# nola4.net
KiCad netlist of a schematic drawn in EAGLE
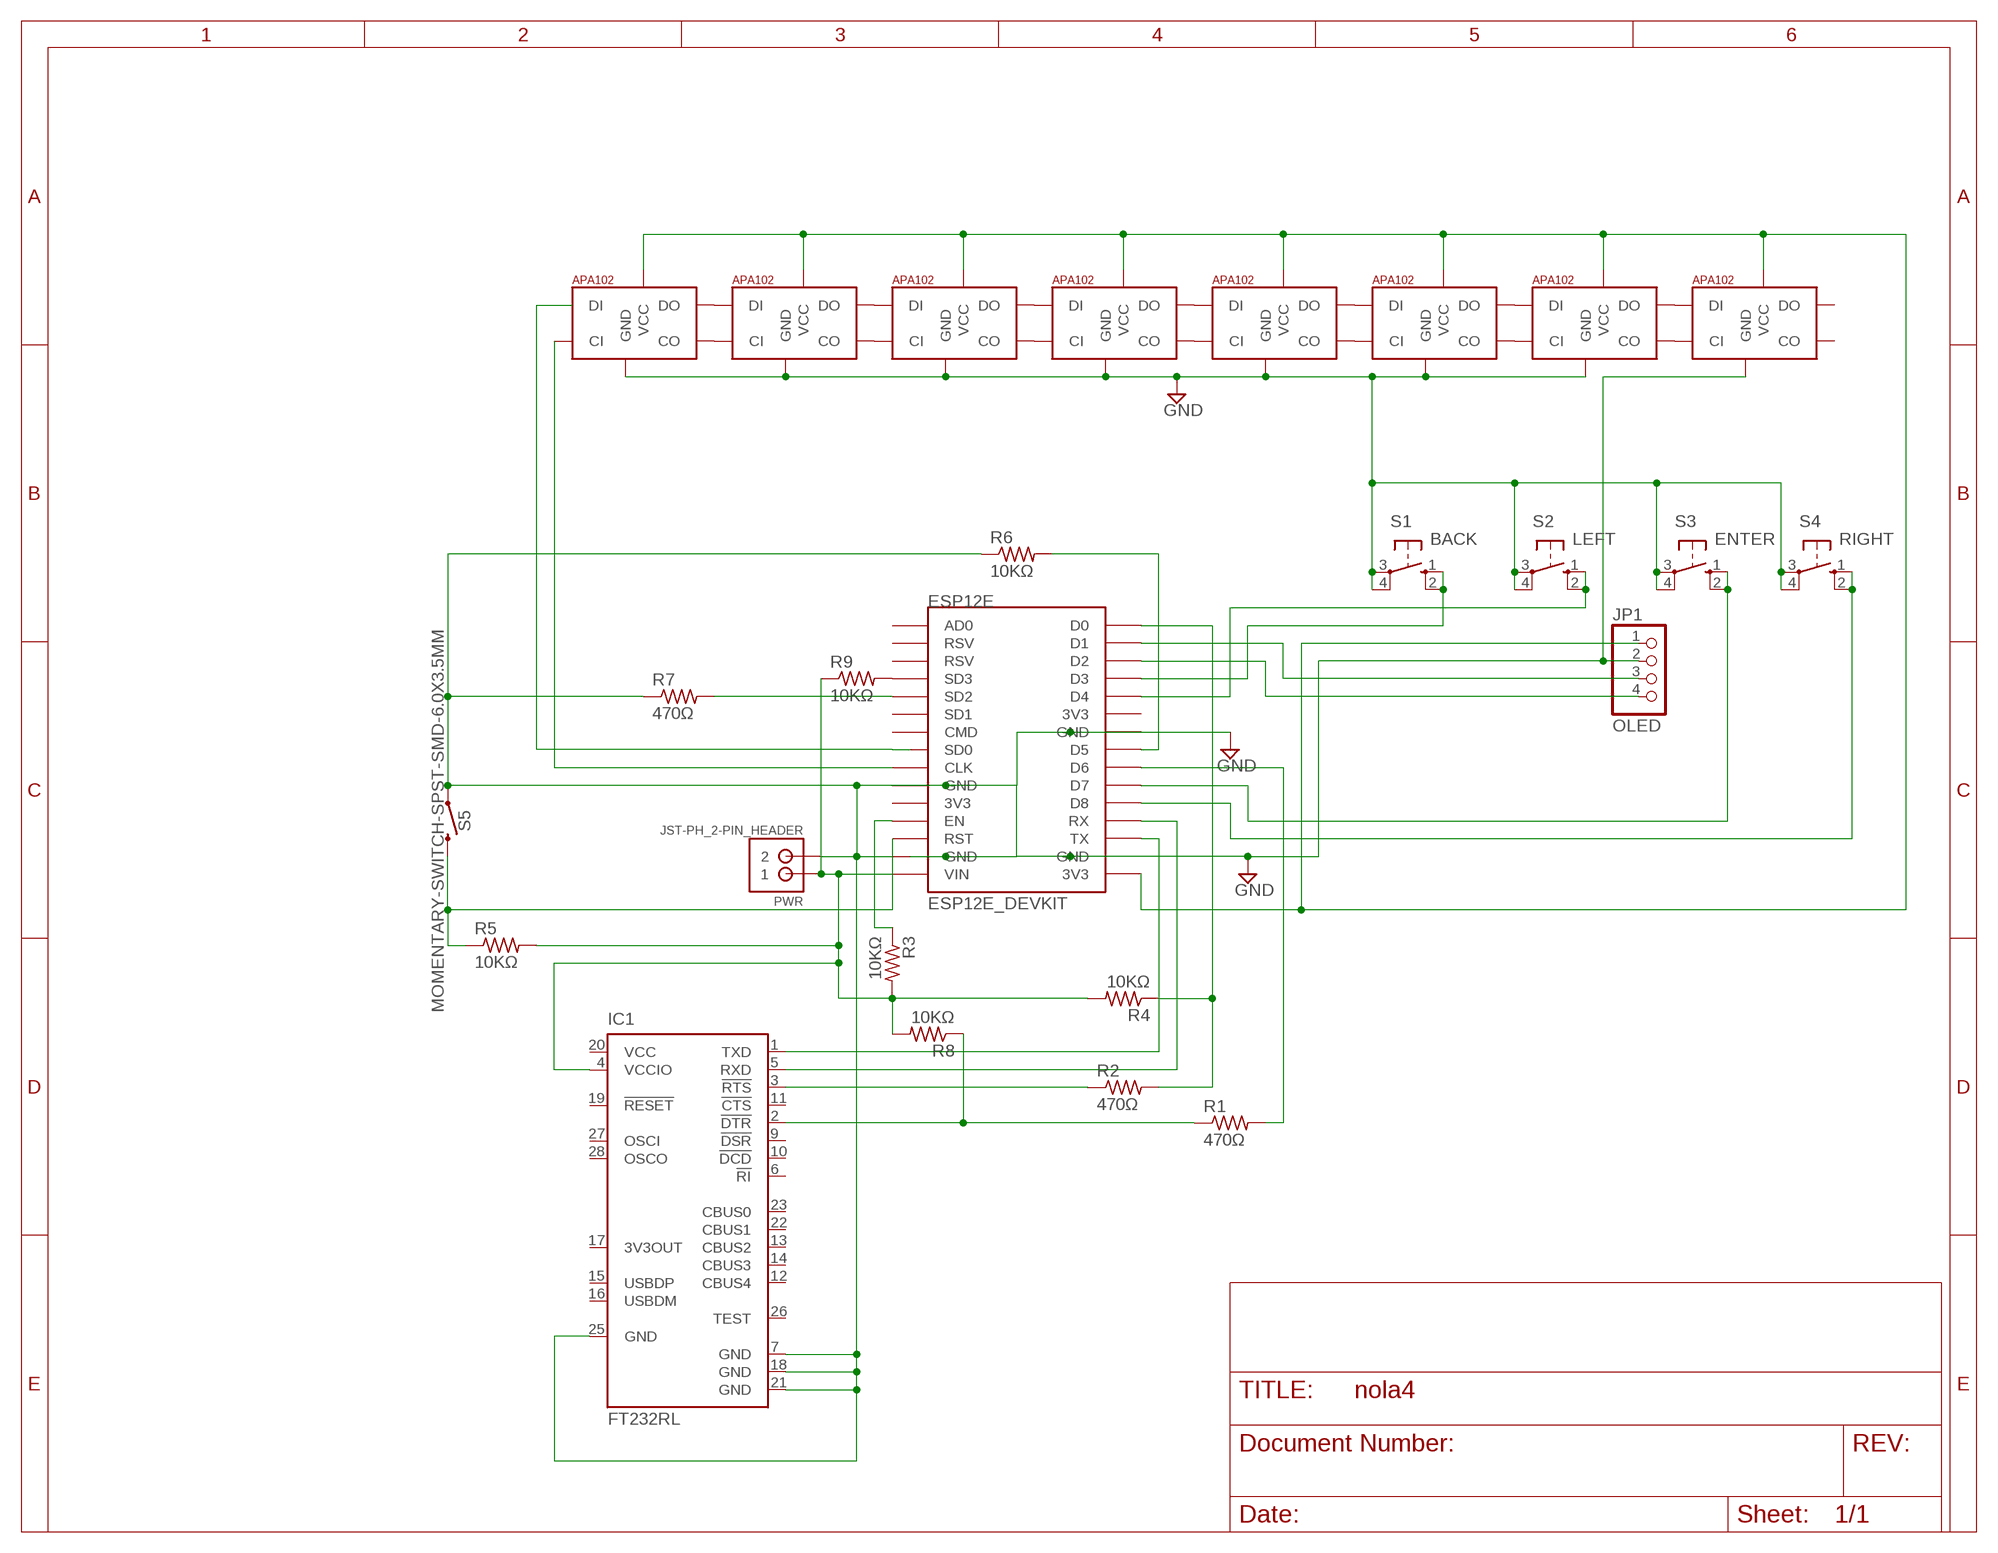
[diagram p0: schematic, sheet 1]

(export (version "E")
  (design (tool "Eeschema 10.0.6"))
  (components
    (comp (ref "ESP12E")
      (value "ESP12E_DEVKIT")
      (footprint "eagle-import:ESP12E_DEVKIT")
      (libsource (lib "eagle-import") (part "ESP12E_DEVKIT"))
    )
    (comp (ref "IC1")
      (value "FT232RL")
      (footprint "eagle-import:SSOP28")
      (libsource (lib "eagle-import") (part "FT232RL"))
    )
    (comp (ref "JP1")
      (value "OLED")
      (footprint "eagle-import:1X04")
      (libsource (lib "eagle-import") (part "PINHD-1X4"))
    )
    (comp (ref "LED1")
      (value "APA1025050")
      (footprint "eagle-import:APA102_5050")
      (libsource (lib "eagle-import") (part "APA1025050"))
    )
    (comp (ref "LED2")
      (value "APA1025050")
      (footprint "eagle-import:APA102_5050")
      (libsource (lib "eagle-import") (part "APA1025050"))
    )
    (comp (ref "LED3")
      (value "APA1025050")
      (footprint "eagle-import:APA102_5050")
      (libsource (lib "eagle-import") (part "APA1025050"))
    )
    (comp (ref "LED4")
      (value "APA1025050")
      (footprint "eagle-import:APA102_5050")
      (libsource (lib "eagle-import") (part "APA1025050"))
    )
    (comp (ref "LED5")
      (value "APA1025050")
      (footprint "eagle-import:APA102_5050")
      (libsource (lib "eagle-import") (part "APA1025050"))
    )
    (comp (ref "LED6")
      (value "APA1025050")
      (footprint "eagle-import:APA102_5050")
      (libsource (lib "eagle-import") (part "APA1025050"))
    )
    (comp (ref "LED7")
      (value "APA1025050")
      (footprint "eagle-import:APA102_5050")
      (libsource (lib "eagle-import") (part "APA1025050"))
    )
    (comp (ref "LED8")
      (value "APA1025050")
      (footprint "eagle-import:APA102_5050")
      (libsource (lib "eagle-import") (part "APA1025050"))
    )
    (comp (ref "PWR")
      (value "JST-PH_2-PIN_HEADER")
      (footprint "eagle-import:JST_B2B-PH_HEADER")
      (libsource (lib "eagle-import") (part "JST-PH_2-PIN_HEADER"))
    )
    (comp (ref "R1")
      (value "470Ω")
      (footprint "eagle-import:R0805")
      (libsource (lib "eagle-import") (part "R-US_R0805"))
    )
    (comp (ref "R2")
      (value "470Ω")
      (footprint "eagle-import:R0805")
      (libsource (lib "eagle-import") (part "R-US_R0805"))
    )
    (comp (ref "R3")
      (value "10KΩ")
      (footprint "eagle-import:R0805")
      (libsource (lib "eagle-import") (part "R-US_R0805"))
    )
    (comp (ref "R4")
      (value "10KΩ")
      (footprint "eagle-import:R0805")
      (libsource (lib "eagle-import") (part "R-US_R0805"))
    )
    (comp (ref "R5")
      (value "10KΩ")
      (footprint "eagle-import:R0805")
      (libsource (lib "eagle-import") (part "R-US_R0805"))
    )
    (comp (ref "R6")
      (value "10KΩ")
      (footprint "eagle-import:R0805")
      (libsource (lib "eagle-import") (part "R-US_R0805"))
    )
    (comp (ref "R7")
      (value "470Ω")
      (footprint "eagle-import:R0805")
      (libsource (lib "eagle-import") (part "R-US_R0805"))
    )
    (comp (ref "R8")
      (value "10KΩ")
      (footprint "eagle-import:R0805")
      (libsource (lib "eagle-import") (part "R-US_R0805"))
    )
    (comp (ref "R9")
      (value "10KΩ")
      (footprint "eagle-import:R0805")
      (libsource (lib "eagle-import") (part "R-US_R0805"))
    )
    (comp (ref "S1")
      (value "BACK")
      (footprint "eagle-import:B3F-10XX")
      (fields (field (name "MPN") "B3F-1000"))
      (libsource (lib "eagle-import") (part "10-XX"))
    )
    (comp (ref "S2")
      (value "LEFT")
      (footprint "eagle-import:B3F-10XX")
      (fields (field (name "MPN") "B3F-1000"))
      (libsource (lib "eagle-import") (part "10-XX"))
    )
    (comp (ref "S3")
      (value "ENTER")
      (footprint "eagle-import:B3F-10XX")
      (fields (field (name "MPN") "B3F-1000"))
      (libsource (lib "eagle-import") (part "10-XX"))
    )
    (comp (ref "S4")
      (value "RIGHT")
      (footprint "eagle-import:B3F-10XX")
      (fields (field (name "MPN") "B3F-1000"))
      (libsource (lib "eagle-import") (part "10-XX"))
    )
    (comp (ref "S5")
      (value "MOMENTARY-SWITCH-SPST-SMD-6.0X3.5MM")
      (footprint "eagle-import:TACTILE_SWITCH_SMD_6.0X3.5MM")
      (libsource (lib "eagle-import") (part "MOMENTARY-SWITCH-SPST-SMD-6.0X3.5MM"))
    )
  )
  (nets
    (net (code "1") (name "/VCC") (class "Default")
      (node (ref "IC1") (pin "20") (pinfunction "VCC_20") (pintype "power_in"))
    )
    (net (code "2") (name "GND") (class "Default")
      (node (ref "ESP12E") (pin "GND@0") (pinfunction "GND_GND@0") (pintype "bidirectional"))
      (node (ref "ESP12E") (pin "GND@1") (pinfunction "GND_GND@1") (pintype "bidirectional"))
      (node (ref "ESP12E") (pin "GND@2") (pinfunction "GND_GND@2") (pintype "bidirectional"))
      (node (ref "ESP12E") (pin "GND@3") (pinfunction "GND_GND@3") (pintype "bidirectional"))
      (node (ref "IC1") (pin "18") (pinfunction "GND_18") (pintype "power_in"))
      (node (ref "IC1") (pin "21") (pinfunction "GND_21") (pintype "power_in"))
      (node (ref "IC1") (pin "25") (pinfunction "GND_25") (pintype "power_in"))
      (node (ref "IC1") (pin "7") (pinfunction "GND_7") (pintype "power_in"))
      (node (ref "JP1") (pin "2") (pinfunction "2_2") (pintype "passive"))
      (node (ref "LED1") (pin "6") (pinfunction "GND_6") (pintype "bidirectional"))
      (node (ref "LED2") (pin "6") (pinfunction "GND_6") (pintype "bidirectional"))
      (node (ref "LED3") (pin "6") (pinfunction "GND_6") (pintype "bidirectional"))
      (node (ref "LED4") (pin "6") (pinfunction "GND_6") (pintype "bidirectional"))
      (node (ref "LED5") (pin "6") (pinfunction "GND_6") (pintype "bidirectional"))
      (node (ref "LED6") (pin "6") (pinfunction "GND_6") (pintype "bidirectional"))
      (node (ref "LED7") (pin "6") (pinfunction "GND_6") (pintype "bidirectional"))
      (node (ref "LED8") (pin "6") (pinfunction "GND_6") (pintype "bidirectional"))
      (node (ref "PWR") (pin "P2") (pinfunction "2_P2") (pintype "bidirectional"))
      (node (ref "R6") (pin "1") (pinfunction "1_1") (pintype "passive"))
      (node (ref "R7") (pin "1") (pinfunction "1_1") (pintype "passive"))
      (node (ref "S1") (pin "3") (pinfunction "P_3") (pintype "passive"))
      (node (ref "S1") (pin "4") (pinfunction "P1_4") (pintype "passive"))
      (node (ref "S2") (pin "3") (pinfunction "P_3") (pintype "passive"))
      (node (ref "S2") (pin "4") (pinfunction "P1_4") (pintype "passive"))
      (node (ref "S3") (pin "3") (pinfunction "P_3") (pintype "passive"))
      (node (ref "S3") (pin "4") (pinfunction "P1_4") (pintype "passive"))
      (node (ref "S4") (pin "3") (pinfunction "P_3") (pintype "passive"))
      (node (ref "S4") (pin "4") (pinfunction "P1_4") (pintype "passive"))
      (node (ref "S5") (pin "1") (pinfunction "1_1") (pintype "passive"))
    )
    (net (code "3") (name "Net-(ESP12E-PadD1)") (class "Default")
      (node (ref "ESP12E") (pin "D1") (pinfunction "D1_D1") (pintype "bidirectional"))
      (node (ref "JP1") (pin "3") (pinfunction "3_3") (pintype "passive"))
    )
    (net (code "4") (name "Net-(ESP12E-PadD2)") (class "Default")
      (node (ref "ESP12E") (pin "D2") (pinfunction "D2_D2") (pintype "bidirectional"))
      (node (ref "JP1") (pin "4") (pinfunction "4_4") (pintype "passive"))
    )
    (net (code "5") (name "Net-(ESP12E-PadD5)") (class "Default")
      (node (ref "ESP12E") (pin "D5") (pinfunction "D5_D5") (pintype "bidirectional"))
      (node (ref "R6") (pin "2") (pinfunction "2_2") (pintype "passive"))
    )
    (net (code "6") (name "Net-(ESP12E-PadD6)") (class "Default")
      (node (ref "ESP12E") (pin "D6") (pinfunction "D6_D6") (pintype "bidirectional"))
      (node (ref "R1") (pin "2") (pinfunction "2_2") (pintype "passive"))
    )
    (net (code "7") (name "Net-(ESP12E-PadEN)") (class "Default")
      (node (ref "ESP12E") (pin "EN") (pinfunction "EN_EN") (pintype "bidirectional"))
      (node (ref "R3") (pin "1") (pinfunction "1_1") (pintype "passive"))
    )
    (net (code "8") (name "Net-(ESP12E-PadRST)") (class "Default")
      (node (ref "ESP12E") (pin "RST") (pinfunction "RST_RST") (pintype "bidirectional"))
      (node (ref "R5") (pin "1") (pinfunction "1_1") (pintype "passive"))
      (node (ref "S5") (pin "2") (pinfunction "2_2") (pintype "passive"))
    )
    (net (code "9") (name "Net-(ESP12E-PadSD2)") (class "Default")
      (node (ref "ESP12E") (pin "SD2") (pinfunction "SD2_SD2") (pintype "bidirectional"))
      (node (ref "R7") (pin "2") (pinfunction "2_2") (pintype "passive"))
    )
    (net (code "10") (name "Net-(ESP12E-PadSD3)") (class "Default")
      (node (ref "ESP12E") (pin "SD3") (pinfunction "SD3_SD3") (pintype "bidirectional"))
      (node (ref "R9") (pin "2") (pinfunction "2_2") (pintype "passive"))
    )
    (net (code "11") (name "Net-(IC1-RXD)") (class "Default")
      (node (ref "ESP12E") (pin "RX") (pinfunction "RX_RX") (pintype "bidirectional"))
      (node (ref "IC1") (pin "5") (pinfunction "RXD_5") (pintype "input"))
    )
    (net (code "12") (name "Net-(IC1-TXD)") (class "Default")
      (node (ref "ESP12E") (pin "D0") (pinfunction "D0_D0") (pintype "bidirectional"))
      (node (ref "ESP12E") (pin "TX") (pinfunction "TX_TX") (pintype "bidirectional"))
      (node (ref "IC1") (pin "1") (pinfunction "TXD_1") (pintype "output"))
      (node (ref "R2") (pin "2") (pinfunction "2_2") (pintype "passive"))
      (node (ref "R4") (pin "1") (pinfunction "1_1") (pintype "passive"))
    )
    (net (code "13") (name "Net-(IC1-VCCIO)") (class "Default")
      (node (ref "ESP12E") (pin "VIN") (pinfunction "VIN_VIN") (pintype "bidirectional"))
      (node (ref "IC1") (pin "4") (pinfunction "VCCIO_4") (pintype "power_in"))
      (node (ref "PWR") (pin "P1") (pinfunction "1_P1") (pintype "bidirectional"))
      (node (ref "R3") (pin "2") (pinfunction "2_2") (pintype "passive"))
      (node (ref "R4") (pin "2") (pinfunction "2_2") (pintype "passive"))
      (node (ref "R5") (pin "2") (pinfunction "2_2") (pintype "passive"))
      (node (ref "R8") (pin "2") (pinfunction "2_2") (pintype "passive"))
      (node (ref "R9") (pin "1") (pinfunction "1_1") (pintype "passive"))
    )
    (net (code "14") (name "Net-(IC1-~{DTR})") (class "Default")
      (node (ref "IC1") (pin "2") (pinfunction "~{DTR}_2") (pintype "output"))
      (node (ref "R1") (pin "1") (pinfunction "1_1") (pintype "passive"))
      (node (ref "R8") (pin "1") (pinfunction "1_1") (pintype "passive"))
    )
    (net (code "15") (name "Net-(IC1-~{RTS})") (class "Default")
      (node (ref "IC1") (pin "3") (pinfunction "~{RTS}_3") (pintype "output"))
      (node (ref "R2") (pin "1") (pinfunction "1_1") (pintype "passive"))
    )
    (net (code "16") (name "Net-(LED1-CI)") (class "Default")
      (node (ref "ESP12E") (pin "CLK") (pinfunction "CLK_CLK") (pintype "bidirectional"))
      (node (ref "LED1") (pin "5") (pinfunction "CI_5") (pintype "bidirectional"))
    )
    (net (code "17") (name "Net-(LED1-CO)") (class "Default")
      (node (ref "LED1") (pin "2") (pinfunction "CO_2") (pintype "bidirectional"))
      (node (ref "LED2") (pin "5") (pinfunction "CI_5") (pintype "bidirectional"))
    )
    (net (code "18") (name "Net-(LED1-DI)") (class "Default")
      (node (ref "ESP12E") (pin "SD0") (pinfunction "SD0_SD0") (pintype "bidirectional"))
      (node (ref "LED1") (pin "4") (pinfunction "DI_4") (pintype "bidirectional"))
    )
    (net (code "19") (name "Net-(LED1-DO)") (class "Default")
      (node (ref "LED1") (pin "3") (pinfunction "DO_3") (pintype "bidirectional"))
      (node (ref "LED2") (pin "4") (pinfunction "DI_4") (pintype "bidirectional"))
    )
    (net (code "20") (name "Net-(LED1-VCC)") (class "Default")
      (node (ref "ESP12E") (pin "3V3@2") (pinfunction "3V3_3V3@2") (pintype "bidirectional"))
      (node (ref "JP1") (pin "1") (pinfunction "1_1") (pintype "passive"))
      (node (ref "LED1") (pin "1") (pinfunction "VCC_1") (pintype "bidirectional"))
      (node (ref "LED2") (pin "1") (pinfunction "VCC_1") (pintype "bidirectional"))
      (node (ref "LED3") (pin "1") (pinfunction "VCC_1") (pintype "bidirectional"))
      (node (ref "LED4") (pin "1") (pinfunction "VCC_1") (pintype "bidirectional"))
      (node (ref "LED5") (pin "1") (pinfunction "VCC_1") (pintype "bidirectional"))
      (node (ref "LED6") (pin "1") (pinfunction "VCC_1") (pintype "bidirectional"))
      (node (ref "LED7") (pin "1") (pinfunction "VCC_1") (pintype "bidirectional"))
      (node (ref "LED8") (pin "1") (pinfunction "VCC_1") (pintype "bidirectional"))
    )
    (net (code "21") (name "Net-(LED2-CO)") (class "Default")
      (node (ref "LED2") (pin "2") (pinfunction "CO_2") (pintype "bidirectional"))
      (node (ref "LED3") (pin "5") (pinfunction "CI_5") (pintype "bidirectional"))
    )
    (net (code "22") (name "Net-(LED2-DO)") (class "Default")
      (node (ref "LED2") (pin "3") (pinfunction "DO_3") (pintype "bidirectional"))
      (node (ref "LED3") (pin "4") (pinfunction "DI_4") (pintype "bidirectional"))
    )
    (net (code "23") (name "Net-(LED3-CO)") (class "Default")
      (node (ref "LED3") (pin "2") (pinfunction "CO_2") (pintype "bidirectional"))
      (node (ref "LED4") (pin "5") (pinfunction "CI_5") (pintype "bidirectional"))
    )
    (net (code "24") (name "Net-(LED3-DO)") (class "Default")
      (node (ref "LED3") (pin "3") (pinfunction "DO_3") (pintype "bidirectional"))
      (node (ref "LED4") (pin "4") (pinfunction "DI_4") (pintype "bidirectional"))
    )
    (net (code "25") (name "Net-(LED4-CO)") (class "Default")
      (node (ref "LED4") (pin "2") (pinfunction "CO_2") (pintype "bidirectional"))
      (node (ref "LED5") (pin "5") (pinfunction "CI_5") (pintype "bidirectional"))
    )
    (net (code "26") (name "Net-(LED4-DO)") (class "Default")
      (node (ref "LED4") (pin "3") (pinfunction "DO_3") (pintype "bidirectional"))
      (node (ref "LED5") (pin "4") (pinfunction "DI_4") (pintype "bidirectional"))
    )
    (net (code "27") (name "Net-(LED5-CO)") (class "Default")
      (node (ref "LED5") (pin "2") (pinfunction "CO_2") (pintype "bidirectional"))
      (node (ref "LED6") (pin "5") (pinfunction "CI_5") (pintype "bidirectional"))
    )
    (net (code "28") (name "Net-(LED5-DO)") (class "Default")
      (node (ref "LED5") (pin "3") (pinfunction "DO_3") (pintype "bidirectional"))
      (node (ref "LED6") (pin "4") (pinfunction "DI_4") (pintype "bidirectional"))
    )
    (net (code "29") (name "Net-(LED6-CO)") (class "Default")
      (node (ref "LED6") (pin "2") (pinfunction "CO_2") (pintype "bidirectional"))
      (node (ref "LED7") (pin "5") (pinfunction "CI_5") (pintype "bidirectional"))
    )
    (net (code "30") (name "Net-(LED6-DO)") (class "Default")
      (node (ref "LED6") (pin "3") (pinfunction "DO_3") (pintype "bidirectional"))
      (node (ref "LED7") (pin "4") (pinfunction "DI_4") (pintype "bidirectional"))
    )
    (net (code "31") (name "Net-(LED7-CO)") (class "Default")
      (node (ref "LED7") (pin "2") (pinfunction "CO_2") (pintype "bidirectional"))
      (node (ref "LED8") (pin "5") (pinfunction "CI_5") (pintype "bidirectional"))
    )
    (net (code "32") (name "Net-(LED7-DO)") (class "Default")
      (node (ref "LED7") (pin "3") (pinfunction "DO_3") (pintype "bidirectional"))
      (node (ref "LED8") (pin "4") (pinfunction "DI_4") (pintype "bidirectional"))
    )
    (net (code "33") (name "Net-(S1-S)") (class "Default")
      (node (ref "ESP12E") (pin "D3") (pinfunction "D3_D3") (pintype "bidirectional"))
      (node (ref "S1") (pin "1") (pinfunction "S_1") (pintype "passive"))
      (node (ref "S1") (pin "2") (pinfunction "S1_2") (pintype "passive"))
    )
    (net (code "34") (name "Net-(S2-S)") (class "Default")
      (node (ref "ESP12E") (pin "D4") (pinfunction "D4_D4") (pintype "bidirectional"))
      (node (ref "S2") (pin "1") (pinfunction "S_1") (pintype "passive"))
      (node (ref "S2") (pin "2") (pinfunction "S1_2") (pintype "passive"))
    )
    (net (code "35") (name "Net-(S3-S)") (class "Default")
      (node (ref "ESP12E") (pin "D7") (pinfunction "D7_D7") (pintype "bidirectional"))
      (node (ref "S3") (pin "1") (pinfunction "S_1") (pintype "passive"))
      (node (ref "S3") (pin "2") (pinfunction "S1_2") (pintype "passive"))
    )
    (net (code "36") (name "Net-(S4-S)") (class "Default")
      (node (ref "ESP12E") (pin "D8") (pinfunction "D8_D8") (pintype "bidirectional"))
      (node (ref "S4") (pin "1") (pinfunction "S_1") (pintype "passive"))
      (node (ref "S4") (pin "2") (pinfunction "S1_2") (pintype "passive"))
    )
    (net (code "37") (name "unconnected-(ESP12E-3V3-Pad3V3@0)") (class "Default")
      (node (ref "ESP12E") (pin "3V3@0") (pinfunction "3V3_3V3@0") (pintype "bidirectional"))
    )
    (net (code "38") (name "unconnected-(ESP12E-3V3-Pad3V3@1)") (class "Default")
      (node (ref "ESP12E") (pin "3V3@1") (pinfunction "3V3_3V3@1") (pintype "bidirectional"))
    )
    (net (code "39") (name "unconnected-(ESP12E-PadAD0)") (class "Default")
      (node (ref "ESP12E") (pin "AD0") (pinfunction "AD0_AD0") (pintype "bidirectional"))
    )
    (net (code "40") (name "unconnected-(ESP12E-PadCMD)") (class "Default")
      (node (ref "ESP12E") (pin "CMD") (pinfunction "CMD_CMD") (pintype "bidirectional"))
    )
    (net (code "41") (name "unconnected-(ESP12E-PadSD1)") (class "Default")
      (node (ref "ESP12E") (pin "SD1") (pinfunction "SD1_SD1") (pintype "bidirectional"))
    )
    (net (code "42") (name "unconnected-(ESP12E-RSV-PadRSV@0)") (class "Default")
      (node (ref "ESP12E") (pin "RSV@0") (pinfunction "RSV_RSV@0") (pintype "bidirectional"))
    )
    (net (code "43") (name "unconnected-(ESP12E-RSV-PadRSV@1)") (class "Default")
      (node (ref "ESP12E") (pin "RSV@1") (pinfunction "RSV_RSV@1") (pintype "bidirectional"))
    )
    (net (code "44") (name "unconnected-(IC1-3V3OUT-Pad17)") (class "Default")
      (node (ref "IC1") (pin "17") (pinfunction "3V3OUT_17") (pintype "output"))
    )
    (net (code "45") (name "unconnected-(IC1-CBUS0-Pad23)") (class "Default")
      (node (ref "IC1") (pin "23") (pinfunction "CBUS0_23") (pintype "bidirectional"))
    )
    (net (code "46") (name "unconnected-(IC1-CBUS1-Pad22)") (class "Default")
      (node (ref "IC1") (pin "22") (pinfunction "CBUS1_22") (pintype "bidirectional"))
    )
    (net (code "47") (name "unconnected-(IC1-CBUS2-Pad13)") (class "Default")
      (node (ref "IC1") (pin "13") (pinfunction "CBUS2_13") (pintype "bidirectional"))
    )
    (net (code "48") (name "unconnected-(IC1-CBUS3-Pad14)") (class "Default")
      (node (ref "IC1") (pin "14") (pinfunction "CBUS3_14") (pintype "bidirectional"))
    )
    (net (code "49") (name "unconnected-(IC1-CBUS4-Pad12)") (class "Default")
      (node (ref "IC1") (pin "12") (pinfunction "CBUS4_12") (pintype "bidirectional"))
    )
    (net (code "50") (name "unconnected-(IC1-OSCI-Pad27)") (class "Default")
      (node (ref "IC1") (pin "27") (pinfunction "OSCI_27") (pintype "input"))
    )
    (net (code "51") (name "unconnected-(IC1-OSCO-Pad28)") (class "Default")
      (node (ref "IC1") (pin "28") (pinfunction "OSCO_28") (pintype "output"))
    )
    (net (code "52") (name "unconnected-(IC1-TEST-Pad26)") (class "Default")
      (node (ref "IC1") (pin "26") (pinfunction "TEST_26") (pintype "input"))
    )
    (net (code "53") (name "unconnected-(IC1-USBDM-Pad16)") (class "Default")
      (node (ref "IC1") (pin "16") (pinfunction "USBDM_16") (pintype "bidirectional"))
    )
    (net (code "54") (name "unconnected-(IC1-USBDP-Pad15)") (class "Default")
      (node (ref "IC1") (pin "15") (pinfunction "USBDP_15") (pintype "bidirectional"))
    )
    (net (code "55") (name "unconnected-(IC1-~{CTS}-Pad11)") (class "Default")
      (node (ref "IC1") (pin "11") (pinfunction "~{CTS}_11") (pintype "input"))
    )
    (net (code "56") (name "unconnected-(IC1-~{DCD}-Pad10)") (class "Default")
      (node (ref "IC1") (pin "10") (pinfunction "~{DCD}_10") (pintype "input"))
    )
    (net (code "57") (name "unconnected-(IC1-~{DSR}-Pad9)") (class "Default")
      (node (ref "IC1") (pin "9") (pinfunction "~{DSR}_9") (pintype "input"))
    )
    (net (code "58") (name "unconnected-(IC1-~{RESET}-Pad19)") (class "Default")
      (node (ref "IC1") (pin "19") (pinfunction "~{RESET}_19") (pintype "input"))
    )
    (net (code "59") (name "unconnected-(IC1-~{RI}-Pad6)") (class "Default")
      (node (ref "IC1") (pin "6") (pinfunction "~{RI}_6") (pintype "input"))
    )
    (net (code "60") (name "unconnected-(LED8-CO-Pad2)") (class "Default")
      (node (ref "LED8") (pin "2") (pinfunction "CO_2") (pintype "bidirectional"))
    )
    (net (code "61") (name "unconnected-(LED8-DO-Pad3)") (class "Default")
      (node (ref "LED8") (pin "3") (pinfunction "DO_3") (pintype "bidirectional"))
    )
  )
)
